# MotorCellOne.net
KiCad netlist of a schematic drawn in Altium Designer
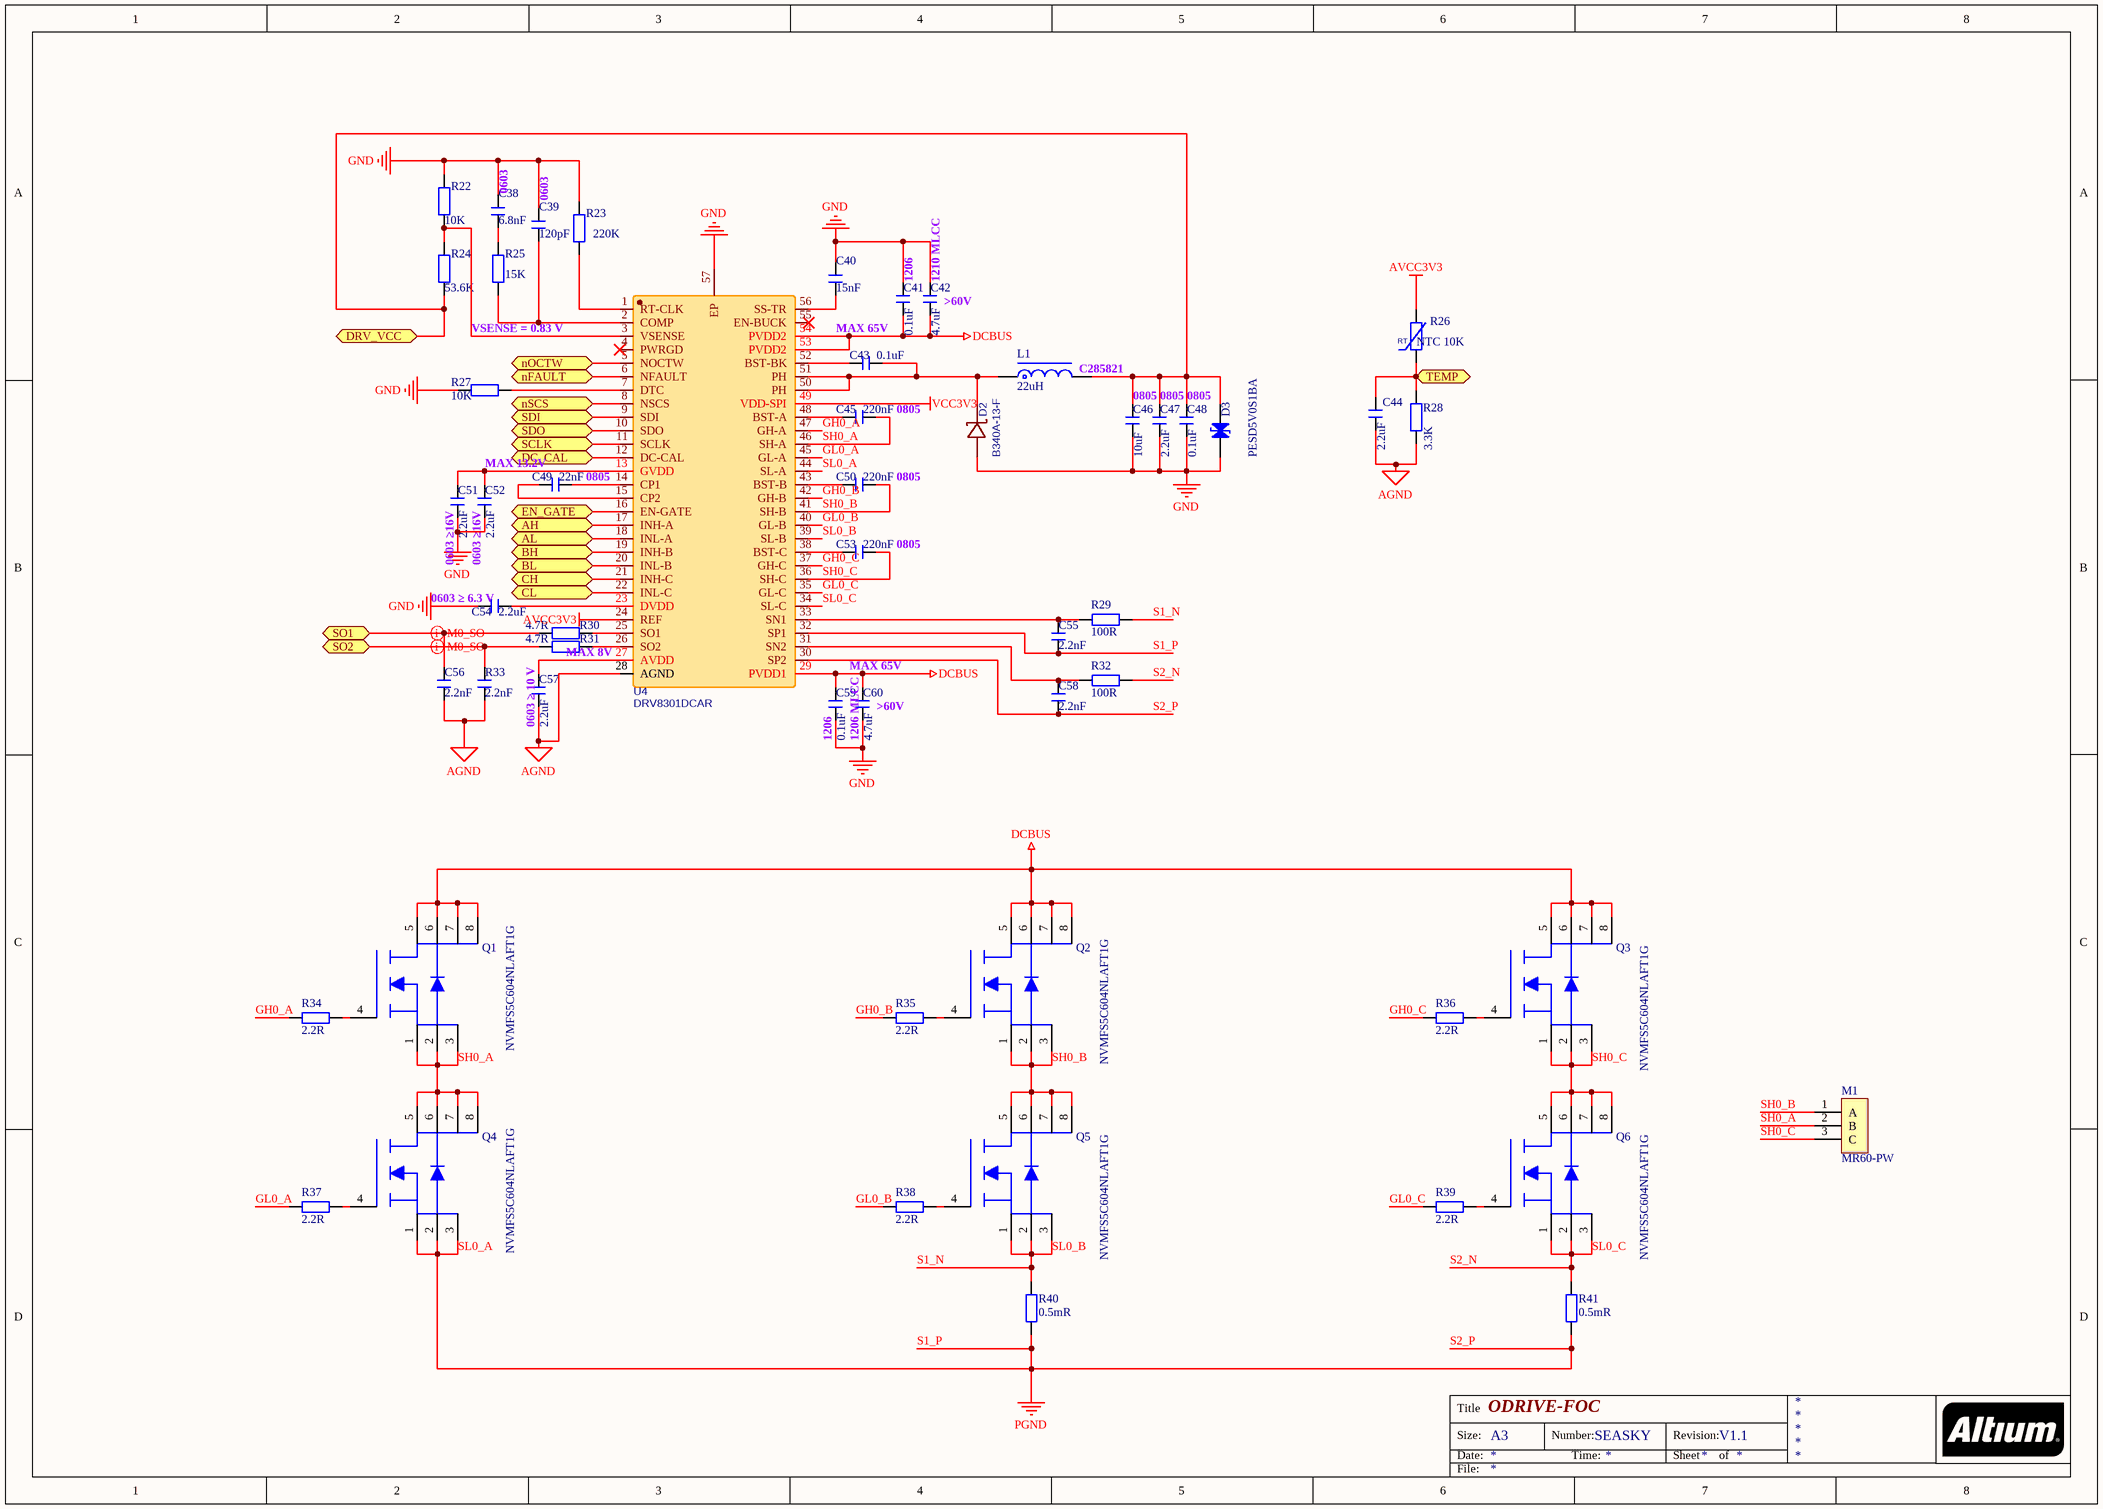
[diagram p0: MotorCellOne.SchDoc]

(export (version "E")
  (design (tool "Eeschema 10.0.6"))
  (components
    (comp (ref "C38")
      (value "6.8nF")
      (footprint "C 0603_L")
      (description "贴片电容")
      (libsource (lib "0.1 - 电阻-电容-电感") (part "C"))
    )
    (comp (ref "C39")
      (value "120pF")
      (footprint "C 0603_L")
      (description "贴片电容")
      (libsource (lib "0.1 - 电阻-电容-电感") (part "C"))
    )
    (comp (ref "C40")
      (value "15nF")
      (footprint "C 0603_L")
      (description "贴片电容")
      (libsource (lib "0.1 - 电阻-电容-电感") (part "C"))
    )
    (comp (ref "C41")
      (value "0.1uF")
      (footprint "C 1206_L")
      (description "贴片电容")
      (libsource (lib "0.1 - 电阻-电容-电感") (part "C"))
    )
    (comp (ref "C42")
      (value "4.7uF")
      (footprint "C 1210_L")
      (description "贴片电容")
      (libsource (lib "0.1 - 电阻-电容-电感") (part "C"))
    )
    (comp (ref "C43")
      (value "0.1uF")
      (footprint "C 0603_L")
      (description "贴片电容")
      (libsource (lib "0.1 - 电阻-电容-电感") (part "C"))
    )
    (comp (ref "C44")
      (value "2.2uF")
      (footprint "C 0603_L")
      (description "贴片电容")
      (libsource (lib "0.1 - 电阻-电容-电感") (part "C"))
    )
    (comp (ref "C45")
      (value "220nF")
      (footprint "C 0805_L")
      (description "贴片电容")
      (libsource (lib "0.1 - 电阻-电容-电感") (part "C"))
    )
    (comp (ref "C46")
      (value "10uF")
      (footprint "C 0805_L")
      (description "贴片电容")
      (libsource (lib "0.1 - 电阻-电容-电感") (part "C"))
    )
    (comp (ref "C47")
      (value "2.2uF")
      (footprint "C 0805_L")
      (description "贴片电容")
      (libsource (lib "0.1 - 电阻-电容-电感") (part "C"))
    )
    (comp (ref "C48")
      (value "0.1uF")
      (footprint "C 0805_L")
      (description "贴片电容")
      (libsource (lib "0.1 - 电阻-电容-电感") (part "C"))
    )
    (comp (ref "C49")
      (value "22nF")
      (footprint "C 0805_L")
      (description "贴片电容")
      (libsource (lib "0.1 - 电阻-电容-电感") (part "C"))
    )
    (comp (ref "C50")
      (value "220nF")
      (footprint "C 0805_L")
      (description "贴片电容")
      (libsource (lib "0.1 - 电阻-电容-电感") (part "C"))
    )
    (comp (ref "C51")
      (value "2.2uF")
      (footprint "C 0603_L")
      (description "贴片电容")
      (libsource (lib "0.1 - 电阻-电容-电感") (part "C"))
    )
    (comp (ref "C52")
      (value "2.2uF")
      (footprint "C 0603_L")
      (description "贴片电容")
      (libsource (lib "0.1 - 电阻-电容-电感") (part "C"))
    )
    (comp (ref "C53")
      (value "220nF")
      (footprint "C 0805_L")
      (description "贴片电容")
      (libsource (lib "0.1 - 电阻-电容-电感") (part "C"))
    )
    (comp (ref "C54")
      (value "2.2uF")
      (footprint "C 0603_L")
      (description "贴片电容")
      (libsource (lib "0.1 - 电阻-电容-电感") (part "C"))
    )
    (comp (ref "C55")
      (value "2.2nF")
      (footprint "C 0603_L")
      (description "贴片电容")
      (libsource (lib "0.1 - 电阻-电容-电感") (part "C"))
    )
    (comp (ref "C56")
      (value "2.2nF")
      (footprint "C 0603_L")
      (description "贴片电容")
      (libsource (lib "0.1 - 电阻-电容-电感") (part "C"))
    )
    (comp (ref "C57")
      (value "2.2uF")
      (footprint "C 0603_L")
      (description "贴片电容")
      (libsource (lib "0.1 - 电阻-电容-电感") (part "C"))
    )
    (comp (ref "C58")
      (value "2.2nF")
      (footprint "C 0603_L")
      (description "贴片电容")
      (libsource (lib "0.1 - 电阻-电容-电感") (part "C"))
    )
    (comp (ref "C59")
      (value "0.1uF")
      (footprint "C 1206_L")
      (description "贴片电容")
      (libsource (lib "0.1 - 电阻-电容-电感") (part "C"))
    )
    (comp (ref "C60")
      (value "4.7uF")
      (footprint "C 1210_L")
      (description "贴片电容")
      (libsource (lib "0.1 - 电阻-电容-电感") (part "C"))
    )
    (comp (ref "D2")
      (value "B340A-13-F")
      (footprint "SMA_L4.4-W2.6-LS5.0-RD")
      (fields (field (name "BOM_SUPPLIER PART") "C85098"))
      (libsource (lib "mx_pcb_library") (part "B340A-13-F"))
    )
    (comp (ref "D3")
      (value "PESD5V0S1BA")
      (footprint "SOD-323")
      (description "PESD5V0S1BA、ESD二极管、5V")
      (libsource (lib "0.2 -  二极管-整流桥") (part "PESD5V0S1BA"))
    )
    (comp (ref "L1")
      (value "22uH")
      (footprint "CD53")
      (description "CD系列贴片线绕功率电感")
      (libsource (lib "0.1 - 电阻-电容-电感") (part "L-SMD"))
    )
    (comp (ref "M1")
      (value "MR60-PW")
      (footprint "MR30-PW")
      (libsource (lib "mx_pcb_library") (part "MR60-PW"))
    )
    (comp (ref "Q1")
      (value "NVMFS5C604NLAFT1G")
      (footprint "PG-TDSON-8_L5.0-W6.0-P1.27-LS6.2-BL-EP")
      (libsource (lib "mx_pcb_library") (part "BSC037N08NS5ATMA1"))
    )
    (comp (ref "Q2")
      (value "NVMFS5C604NLAFT1G")
      (footprint "PG-TDSON-8_L5.0-W6.0-P1.27-LS6.2-BL-EP")
      (libsource (lib "mx_pcb_library") (part "BSC037N08NS5ATMA1"))
    )
    (comp (ref "Q3")
      (value "NVMFS5C604NLAFT1G")
      (footprint "PG-TDSON-8_L5.0-W6.0-P1.27-LS6.2-BL-EP")
      (libsource (lib "mx_pcb_library") (part "BSC037N08NS5ATMA1"))
    )
    (comp (ref "Q4")
      (value "NVMFS5C604NLAFT1G")
      (footprint "PG-TDSON-8_L5.0-W6.0-P1.27-LS6.2-BL-EP")
      (libsource (lib "mx_pcb_library") (part "BSC037N08NS5ATMA1"))
    )
    (comp (ref "Q5")
      (value "NVMFS5C604NLAFT1G")
      (footprint "PG-TDSON-8_L5.0-W6.0-P1.27-LS6.2-BL-EP")
      (libsource (lib "mx_pcb_library") (part "BSC037N08NS5ATMA1"))
    )
    (comp (ref "Q6")
      (value "NVMFS5C604NLAFT1G")
      (footprint "PG-TDSON-8_L5.0-W6.0-P1.27-LS6.2-BL-EP")
      (libsource (lib "mx_pcb_library") (part "BSC037N08NS5ATMA1"))
    )
    (comp (ref "R22")
      (value "10K")
      (footprint "R 0603_L")
      (description "贴片电阻")
      (libsource (lib "0.1 - 电阻-电容-电感") (part "R"))
    )
    (comp (ref "R23")
      (value "220K")
      (footprint "R 0603_L")
      (description "贴片电阻")
      (libsource (lib "0.1 - 电阻-电容-电感") (part "R"))
    )
    (comp (ref "R24")
      (value "53.6K")
      (footprint "R 0603_L")
      (description "贴片电阻")
      (libsource (lib "0.1 - 电阻-电容-电感") (part "R"))
    )
    (comp (ref "R25")
      (value "15K")
      (footprint "R 0603_L")
      (description "贴片电阻")
      (libsource (lib "0.1 - 电阻-电容-电感") (part "R"))
    )
    (comp (ref "R26")
      (value "NTC 10K")
      (footprint "R 0805-HP_L")
      (description "热敏电阻")
      (libsource (lib "0.1 - 电阻-电容-电感") (part "RT"))
    )
    (comp (ref "R27")
      (value "10K")
      (footprint "R 0603_L")
      (description "贴片电阻")
      (libsource (lib "0.1 - 电阻-电容-电感") (part "R"))
    )
    (comp (ref "R28")
      (value "3.3K")
      (footprint "R 0805_L")
      (description "贴片电阻")
      (libsource (lib "0.1 - 电阻-电容-电感") (part "R"))
    )
    (comp (ref "R29")
      (value "100R")
      (footprint "R 0603_L")
      (description "贴片电阻")
      (libsource (lib "0.1 - 电阻-电容-电感") (part "R"))
    )
    (comp (ref "R30")
      (value "4.7R")
      (footprint "R 0603_L")
      (description "贴片电阻")
      (libsource (lib "0.1 - 电阻-电容-电感") (part "R"))
    )
    (comp (ref "R31")
      (value "4.7R")
      (footprint "R 0603_L")
      (description "贴片电阻")
      (libsource (lib "0.1 - 电阻-电容-电感") (part "R"))
    )
    (comp (ref "R32")
      (value "100R")
      (footprint "R 0603_L")
      (description "贴片电阻")
      (libsource (lib "0.1 - 电阻-电容-电感") (part "R"))
    )
    (comp (ref "R33")
      (value "2.2nF")
      (footprint "C 0603_L")
      (description "贴片电容")
      (libsource (lib "0.1 - 电阻-电容-电感") (part "C"))
    )
    (comp (ref "R34")
      (value "2.2R")
      (footprint "R 0603_L")
      (description "贴片电阻")
      (libsource (lib "0.1 - 电阻-电容-电感") (part "R"))
    )
    (comp (ref "R35")
      (value "2.2R")
      (footprint "R 0603_L")
      (description "贴片电阻")
      (libsource (lib "0.1 - 电阻-电容-电感") (part "R"))
    )
    (comp (ref "R36")
      (value "2.2R")
      (footprint "R 0603_L")
      (description "贴片电阻")
      (libsource (lib "0.1 - 电阻-电容-电感") (part "R"))
    )
    (comp (ref "R37")
      (value "2.2R")
      (footprint "R 0603_L")
      (description "贴片电阻")
      (libsource (lib "0.1 - 电阻-电容-电感") (part "R"))
    )
    (comp (ref "R38")
      (value "2.2R")
      (footprint "R 0603_L")
      (description "贴片电阻")
      (libsource (lib "0.1 - 电阻-电容-电感") (part "R"))
    )
    (comp (ref "R39")
      (value "2.2R")
      (footprint "R 0603_L")
      (description "贴片电阻")
      (libsource (lib "0.1 - 电阻-电容-电感") (part "R"))
    )
    (comp (ref "R40")
      (value "0.5mR")
      (footprint "R3920")
      (description "精密贴片电阻")
      (libsource (lib "0.1 - 电阻-电容-电感") (part "R-Precision"))
    )
    (comp (ref "R41")
      (value "0.5mR")
      (footprint "R3920")
      (description "精密贴片电阻")
      (libsource (lib "0.1 - 电阻-电容-电感") (part "R-Precision"))
    )
    (comp (ref "U4")
      (value "DRV8301DCAR")
      (footprint "HTSSOP-56_L14.0-W6.0-P0.50-LS8.0-BL")
      (fields (field (name "BOM_SUPPLIER PART") "C98969") (field (name "CONTRIBUTOR") "LCSC"))
      (libsource (lib "mx_pcb_library") (part "DRV8301DCAR"))
    )
  )
  (nets
    (net (code "1") (name "/AH") (class "Default")
      (node (ref "U4") (pin "17") (pinfunction "INH-A_17") (pintype "passive"))
    )
    (net (code "2") (name "/AL") (class "Default")
      (node (ref "U4") (pin "18") (pinfunction "INL-A_18") (pintype "passive"))
    )
    (net (code "3") (name "/BH") (class "Default")
      (node (ref "U4") (pin "19") (pinfunction "INH-B_19") (pintype "passive"))
    )
    (net (code "4") (name "/BL") (class "Default")
      (node (ref "U4") (pin "20") (pinfunction "INL-B_20") (pintype "passive"))
    )
    (net (code "5") (name "/CH") (class "Default")
      (node (ref "U4") (pin "21") (pinfunction "INH-C_21") (pintype "passive"))
    )
    (net (code "6") (name "/CL") (class "Default")
      (node (ref "U4") (pin "22") (pinfunction "INL-C_22") (pintype "passive"))
    )
    (net (code "7") (name "/DC_CAL") (class "Default")
      (node (ref "U4") (pin "12") (pinfunction "DC-CAL_12") (pintype "passive"))
    )
    (net (code "8") (name "/DRV_VCC") (class "Default")
      (node (ref "C46") (pin "2") (pinfunction "2_2") (pintype "passive"))
      (node (ref "C47") (pin "2") (pinfunction "2_2") (pintype "passive"))
      (node (ref "C48") (pin "2") (pinfunction "2_2") (pintype "passive"))
      (node (ref "D3") (pin "1") (pinfunction "A_1") (pintype "passive"))
      (node (ref "L1") (pin "2") (pinfunction "2_2") (pintype "passive"))
      (node (ref "R24") (pin "1") (pinfunction "1_1") (pintype "passive"))
    )
    (net (code "9") (name "/EN_GATE") (class "Default")
      (node (ref "U4") (pin "16") (pinfunction "EN-GATE_16") (pintype "passive"))
    )
    (net (code "10") (name "/GH0_A") (class "Default")
      (node (ref "R34") (pin "1") (pinfunction "1_1") (pintype "passive"))
      (node (ref "U4") (pin "47") (pinfunction "GH-A_47") (pintype "passive"))
    )
    (net (code "11") (name "/GH0_B") (class "Default")
      (node (ref "R35") (pin "1") (pinfunction "1_1") (pintype "passive"))
      (node (ref "U4") (pin "42") (pinfunction "GH-B_42") (pintype "passive"))
    )
    (net (code "12") (name "/GH0_C") (class "Default")
      (node (ref "R36") (pin "1") (pinfunction "1_1") (pintype "passive"))
      (node (ref "U4") (pin "37") (pinfunction "GH-C_37") (pintype "passive"))
    )
    (net (code "13") (name "/GL0_A") (class "Default")
      (node (ref "R37") (pin "1") (pinfunction "1_1") (pintype "passive"))
      (node (ref "U4") (pin "45") (pinfunction "GL-A_45") (pintype "passive"))
    )
    (net (code "14") (name "/GL0_B") (class "Default")
      (node (ref "R38") (pin "1") (pinfunction "1_1") (pintype "passive"))
      (node (ref "U4") (pin "40") (pinfunction "GL-B_40") (pintype "passive"))
    )
    (net (code "15") (name "/GL0_C") (class "Default")
      (node (ref "R39") (pin "1") (pinfunction "1_1") (pintype "passive"))
      (node (ref "U4") (pin "35") (pinfunction "GL-C_35") (pintype "passive"))
    )
    (net (code "16") (name "/S1_N") (class "Default")
      (node (ref "Q5") (pin "1") (pinfunction "1_1") (pintype "passive"))
      (node (ref "Q5") (pin "2") (pinfunction "2_2") (pintype "passive"))
      (node (ref "Q5") (pin "3") (pinfunction "3_3") (pintype "passive"))
      (node (ref "R29") (pin "2") (pinfunction "2_2") (pintype "passive"))
      (node (ref "R40") (pin "2") (pinfunction "2_2") (pintype "passive"))
      (node (ref "U4") (pin "39") (pinfunction "SL-B_39") (pintype "passive"))
    )
    (net (code "17") (name "/S2_N") (class "Default")
      (node (ref "Q6") (pin "1") (pinfunction "1_1") (pintype "passive"))
      (node (ref "Q6") (pin "2") (pinfunction "2_2") (pintype "passive"))
      (node (ref "Q6") (pin "3") (pinfunction "3_3") (pintype "passive"))
      (node (ref "R32") (pin "2") (pinfunction "2_2") (pintype "passive"))
      (node (ref "R41") (pin "2") (pinfunction "2_2") (pintype "passive"))
      (node (ref "U4") (pin "34") (pinfunction "SL-C_34") (pintype "passive"))
    )
    (net (code "18") (name "/SCLK") (class "Default")
      (node (ref "U4") (pin "11") (pinfunction "SCLK_11") (pintype "passive"))
    )
    (net (code "19") (name "/SDI") (class "Default")
      (node (ref "U4") (pin "9") (pinfunction "SDI_9") (pintype "passive"))
    )
    (net (code "20") (name "/SDO") (class "Default")
      (node (ref "U4") (pin "10") (pinfunction "SDO_10") (pintype "passive"))
    )
    (net (code "21") (name "/SH0_A") (class "Default")
      (node (ref "C45") (pin "2") (pinfunction "2_2") (pintype "passive"))
      (node (ref "M1") (pin "2") (pinfunction "B_2") (pintype "passive"))
      (node (ref "Q1") (pin "1") (pinfunction "1_1") (pintype "passive"))
      (node (ref "Q1") (pin "2") (pinfunction "2_2") (pintype "passive"))
      (node (ref "Q1") (pin "3") (pinfunction "3_3") (pintype "passive"))
      (node (ref "Q4") (pin "5") (pinfunction "5_5") (pintype "passive"))
      (node (ref "Q4") (pin "6") (pinfunction "6_6") (pintype "passive"))
      (node (ref "Q4") (pin "7") (pinfunction "7_7") (pintype "passive"))
      (node (ref "Q4") (pin "8") (pinfunction "8_8") (pintype "passive"))
      (node (ref "U4") (pin "46") (pinfunction "SH-A_46") (pintype "passive"))
    )
    (net (code "22") (name "/SH0_B") (class "Default")
      (node (ref "C50") (pin "2") (pinfunction "2_2") (pintype "passive"))
      (node (ref "M1") (pin "1") (pinfunction "A_1") (pintype "passive"))
      (node (ref "Q2") (pin "1") (pinfunction "1_1") (pintype "passive"))
      (node (ref "Q2") (pin "2") (pinfunction "2_2") (pintype "passive"))
      (node (ref "Q2") (pin "3") (pinfunction "3_3") (pintype "passive"))
      (node (ref "Q5") (pin "5") (pinfunction "5_5") (pintype "passive"))
      (node (ref "Q5") (pin "6") (pinfunction "6_6") (pintype "passive"))
      (node (ref "Q5") (pin "7") (pinfunction "7_7") (pintype "passive"))
      (node (ref "Q5") (pin "8") (pinfunction "8_8") (pintype "passive"))
      (node (ref "U4") (pin "41") (pinfunction "SH-B_41") (pintype "passive"))
    )
    (net (code "23") (name "/SH0_C") (class "Default")
      (node (ref "C53") (pin "2") (pinfunction "2_2") (pintype "passive"))
      (node (ref "M1") (pin "3") (pinfunction "C_3") (pintype "passive"))
      (node (ref "Q3") (pin "1") (pinfunction "1_1") (pintype "passive"))
      (node (ref "Q3") (pin "2") (pinfunction "2_2") (pintype "passive"))
      (node (ref "Q3") (pin "3") (pinfunction "3_3") (pintype "passive"))
      (node (ref "Q6") (pin "5") (pinfunction "5_5") (pintype "passive"))
      (node (ref "Q6") (pin "6") (pinfunction "6_6") (pintype "passive"))
      (node (ref "Q6") (pin "7") (pinfunction "7_7") (pintype "passive"))
      (node (ref "Q6") (pin "8") (pinfunction "8_8") (pintype "passive"))
      (node (ref "U4") (pin "36") (pinfunction "SH-C_36") (pintype "passive"))
    )
    (net (code "24") (name "/SO1") (class "Default")
      (node (ref "C56") (pin "2") (pinfunction "2_2") (pintype "passive"))
      (node (ref "R30") (pin "1") (pinfunction "1_1") (pintype "passive"))
    )
    (net (code "25") (name "/SO2") (class "Default")
      (node (ref "R31") (pin "1") (pinfunction "1_1") (pintype "passive"))
      (node (ref "R33") (pin "2") (pinfunction "2_2") (pintype "passive"))
    )
    (net (code "26") (name "/TEMP") (class "Default")
      (node (ref "C44") (pin "1") (pinfunction "1_1") (pintype "passive"))
      (node (ref "R26") (pin "1") (pinfunction "1_1") (pintype "passive"))
      (node (ref "R28") (pin "2") (pinfunction "2_2") (pintype "passive"))
    )
    (net (code "27") (name "/nFAULT") (class "Default")
      (node (ref "U4") (pin "6") (pinfunction "NFAULT_6") (pintype "passive"))
    )
    (net (code "28") (name "/nOCTW") (class "Default")
      (node (ref "U4") (pin "5") (pinfunction "NOCTW_5") (pintype "passive"))
    )
    (net (code "29") (name "/nSCS") (class "Default")
      (node (ref "U4") (pin "8") (pinfunction "NSCS_8") (pintype "passive"))
    )
    (net (code "30") (name "AGND") (class "Default")
      (node (ref "C44") (pin "2") (pinfunction "2_2") (pintype "passive"))
      (node (ref "C56") (pin "1") (pinfunction "1_1") (pintype "passive"))
      (node (ref "C57") (pin "1") (pinfunction "1_1") (pintype "passive"))
      (node (ref "R28") (pin "1") (pinfunction "1_1") (pintype "passive"))
      (node (ref "R33") (pin "1") (pinfunction "1_1") (pintype "passive"))
      (node (ref "U4") (pin "28") (pinfunction "AGND_28") (pintype "passive"))
    )
    (net (code "31") (name "AVCC3V3") (class "Default")
      (node (ref "R26") (pin "2") (pinfunction "2_2") (pintype "passive"))
      (node (ref "U4") (pin "24") (pinfunction "REF_24") (pintype "passive"))
    )
    (net (code "32") (name "DCBUS") (class "Default")
      (node (ref "C41") (pin "1") (pinfunction "1_1") (pintype "passive"))
      (node (ref "C42") (pin "1") (pinfunction "1_1") (pintype "passive"))
      (node (ref "C59") (pin "2") (pinfunction "2_2") (pintype "passive"))
      (node (ref "C60") (pin "2") (pinfunction "2_2") (pintype "passive"))
      (node (ref "Q1") (pin "5") (pinfunction "5_5") (pintype "passive"))
      (node (ref "Q1") (pin "6") (pinfunction "6_6") (pintype "passive"))
      (node (ref "Q1") (pin "7") (pinfunction "7_7") (pintype "passive"))
      (node (ref "Q1") (pin "8") (pinfunction "8_8") (pintype "passive"))
      (node (ref "Q2") (pin "5") (pinfunction "5_5") (pintype "passive"))
      (node (ref "Q2") (pin "6") (pinfunction "6_6") (pintype "passive"))
      (node (ref "Q2") (pin "7") (pinfunction "7_7") (pintype "passive"))
      (node (ref "Q2") (pin "8") (pinfunction "8_8") (pintype "passive"))
      (node (ref "Q3") (pin "5") (pinfunction "5_5") (pintype "passive"))
      (node (ref "Q3") (pin "6") (pinfunction "6_6") (pintype "passive"))
      (node (ref "Q3") (pin "7") (pinfunction "7_7") (pintype "passive"))
      (node (ref "Q3") (pin "8") (pinfunction "8_8") (pintype "passive"))
      (node (ref "U4") (pin "29") (pinfunction "PVDD1_29") (pintype "passive"))
      (node (ref "U4") (pin "53") (pinfunction "PVDD2_53") (pintype "passive"))
      (node (ref "U4") (pin "54") (pinfunction "PVDD2_54") (pintype "passive"))
    )
    (net (code "33") (name "GND") (class "Default")
      (node (ref "C38") (pin "1") (pinfunction "1_1") (pintype "passive"))
      (node (ref "C39") (pin "1") (pinfunction "1_1") (pintype "passive"))
      (node (ref "C40") (pin "1") (pinfunction "1_1") (pintype "passive"))
      (node (ref "C41") (pin "2") (pinfunction "2_2") (pintype "passive"))
      (node (ref "C42") (pin "2") (pinfunction "2_2") (pintype "passive"))
      (node (ref "C46") (pin "1") (pinfunction "1_1") (pintype "passive"))
      (node (ref "C47") (pin "1") (pinfunction "1_1") (pintype "passive"))
      (node (ref "C48") (pin "1") (pinfunction "1_1") (pintype "passive"))
      (node (ref "C51") (pin "1") (pinfunction "1_1") (pintype "passive"))
      (node (ref "C52") (pin "1") (pinfunction "1_1") (pintype "passive"))
      (node (ref "C54") (pin "1") (pinfunction "1_1") (pintype "passive"))
      (node (ref "C59") (pin "1") (pinfunction "1_1") (pintype "passive"))
      (node (ref "C60") (pin "1") (pinfunction "1_1") (pintype "passive"))
      (node (ref "D2") (pin "2") (pinfunction "A_2") (pintype "passive"))
      (node (ref "D3") (pin "2") (pinfunction "K_2") (pintype "passive"))
      (node (ref "R22") (pin "2") (pinfunction "2_2") (pintype "passive"))
      (node (ref "R23") (pin "2") (pinfunction "2_2") (pintype "passive"))
      (node (ref "R27") (pin "2") (pinfunction "2_2") (pintype "passive"))
      (node (ref "U4") (pin "57") (pinfunction "EP_57") (pintype "passive"))
    )
    (net (code "34") (name "Net-(C38-Pad2)") (class "Default")
      (node (ref "C38") (pin "2") (pinfunction "2_2") (pintype "passive"))
      (node (ref "R25") (pin "2") (pinfunction "2_2") (pintype "passive"))
    )
    (net (code "35") (name "Net-(D2-K)") (class "Default")
      (node (ref "C43") (pin "1") (pinfunction "1_1") (pintype "passive"))
      (node (ref "D2") (pin "1") (pinfunction "K_1") (pintype "passive"))
      (node (ref "L1") (pin "1") (pinfunction "1_1") (pintype "passive"))
      (node (ref "U4") (pin "50") (pinfunction "PH_50") (pintype "passive"))
      (node (ref "U4") (pin "51") (pinfunction "PH_51") (pintype "passive"))
    )
    (net (code "36") (name "Net-(Q1-Pad4)") (class "Default")
      (node (ref "Q1") (pin "4") (pinfunction "4_4") (pintype "passive"))
      (node (ref "R34") (pin "2") (pinfunction "2_2") (pintype "passive"))
    )
    (net (code "37") (name "Net-(Q2-Pad4)") (class "Default")
      (node (ref "Q2") (pin "4") (pinfunction "4_4") (pintype "passive"))
      (node (ref "R35") (pin "2") (pinfunction "2_2") (pintype "passive"))
    )
    (net (code "38") (name "Net-(Q3-Pad4)") (class "Default")
      (node (ref "Q3") (pin "4") (pinfunction "4_4") (pintype "passive"))
      (node (ref "R36") (pin "2") (pinfunction "2_2") (pintype "passive"))
    )
    (net (code "39") (name "Net-(Q4-Pad4)") (class "Default")
      (node (ref "Q4") (pin "4") (pinfunction "4_4") (pintype "passive"))
      (node (ref "R37") (pin "2") (pinfunction "2_2") (pintype "passive"))
    )
    (net (code "40") (name "Net-(Q5-Pad4)") (class "Default")
      (node (ref "Q5") (pin "4") (pinfunction "4_4") (pintype "passive"))
      (node (ref "R38") (pin "2") (pinfunction "2_2") (pintype "passive"))
    )
    (net (code "41") (name "Net-(Q6-Pad4)") (class "Default")
      (node (ref "Q6") (pin "4") (pinfunction "4_4") (pintype "passive"))
      (node (ref "R39") (pin "2") (pinfunction "2_2") (pintype "passive"))
    )
    (net (code "42") (name "Net-(U4-AVDD)") (class "Default")
      (node (ref "C57") (pin "2") (pinfunction "2_2") (pintype "passive"))
      (node (ref "U4") (pin "27") (pinfunction "AVDD_27") (pintype "passive"))
    )
    (net (code "43") (name "Net-(U4-BST-A)") (class "Default")
      (node (ref "C45") (pin "1") (pinfunction "1_1") (pintype "passive"))
      (node (ref "U4") (pin "48") (pinfunction "BST-A_48") (pintype "passive"))
    )
    (net (code "44") (name "Net-(U4-BST-B)") (class "Default")
      (node (ref "C50") (pin "1") (pinfunction "1_1") (pintype "passive"))
      (node (ref "U4") (pin "43") (pinfunction "BST-B_43") (pintype "passive"))
    )
    (net (code "45") (name "Net-(U4-BST-BK)") (class "Default")
      (node (ref "C43") (pin "2") (pinfunction "2_2") (pintype "passive"))
      (node (ref "U4") (pin "52") (pinfunction "BST-BK_52") (pintype "passive"))
    )
    (net (code "46") (name "Net-(U4-BST-C)") (class "Default")
      (node (ref "C53") (pin "1") (pinfunction "1_1") (pintype "passive"))
      (node (ref "U4") (pin "38") (pinfunction "BST-C_38") (pintype "passive"))
    )
    (net (code "47") (name "Net-(U4-COMP)") (class "Default")
      (node (ref "C39") (pin "2") (pinfunction "2_2") (pintype "passive"))
      (node (ref "R25") (pin "1") (pinfunction "1_1") (pintype "passive"))
      (node (ref "U4") (pin "2") (pinfunction "COMP_2") (pintype "passive"))
    )
    (net (code "48") (name "Net-(U4-CP1)") (class "Default")
      (node (ref "C49") (pin "1") (pinfunction "1_1") (pintype "passive"))
      (node (ref "U4") (pin "14") (pinfunction "CP1_14") (pintype "passive"))
    )
    (net (code "49") (name "Net-(U4-CP2)") (class "Default")
      (node (ref "C49") (pin "2") (pinfunction "2_2") (pintype "passive"))
      (node (ref "U4") (pin "15") (pinfunction "CP2_15") (pintype "passive"))
    )
    (net (code "50") (name "Net-(U4-DTC)") (class "Default")
      (node (ref "R27") (pin "1") (pinfunction "1_1") (pintype "passive"))
      (node (ref "U4") (pin "7") (pinfunction "DTC_7") (pintype "passive"))
    )
    (net (code "51") (name "Net-(U4-DVDD)") (class "Default")
      (node (ref "C54") (pin "2") (pinfunction "2_2") (pintype "passive"))
      (node (ref "U4") (pin "23") (pinfunction "DVDD_23") (pintype "passive"))
    )
    (net (code "52") (name "Net-(U4-GVDD)") (class "Default")
      (node (ref "C51") (pin "2") (pinfunction "2_2") (pintype "passive"))
      (node (ref "C52") (pin "2") (pinfunction "2_2") (pintype "passive"))
      (node (ref "U4") (pin "13") (pinfunction "GVDD_13") (pintype "passive"))
    )
    (net (code "53") (name "Net-(U4-RT-CLK)") (class "Default")
      (node (ref "R23") (pin "1") (pinfunction "1_1") (pintype "passive"))
      (node (ref "U4") (pin "1") (pinfunction "RT-CLK_1") (pintype "passive"))
    )
    (net (code "54") (name "Net-(U4-SN1)") (class "Default")
      (node (ref "C55") (pin "2") (pinfunction "2_2") (pintype "passive"))
      (node (ref "R29") (pin "1") (pinfunction "1_1") (pintype "passive"))
      (node (ref "U4") (pin "33") (pinfunction "SN1_33") (pintype "passive"))
    )
    (net (code "55") (name "Net-(U4-SN2)") (class "Default")
      (node (ref "C58") (pin "2") (pinfunction "2_2") (pintype "passive"))
      (node (ref "R32") (pin "1") (pinfunction "1_1") (pintype "passive"))
      (node (ref "U4") (pin "31") (pinfunction "SN2_31") (pintype "passive"))
    )
    (net (code "56") (name "Net-(U4-SO1)") (class "Default")
      (node (ref "R30") (pin "2") (pinfunction "2_2") (pintype "passive"))
      (node (ref "U4") (pin "25") (pinfunction "SO1_25") (pintype "passive"))
    )
    (net (code "57") (name "Net-(U4-SO2)") (class "Default")
      (node (ref "R31") (pin "2") (pinfunction "2_2") (pintype "passive"))
      (node (ref "U4") (pin "26") (pinfunction "SO2_26") (pintype "passive"))
    )
    (net (code "58") (name "Net-(U4-SS-TR)") (class "Default")
      (node (ref "C40") (pin "2") (pinfunction "2_2") (pintype "passive"))
      (node (ref "U4") (pin "56") (pinfunction "SS-TR_56") (pintype "passive"))
    )
    (net (code "59") (name "Net-(U4-VSENSE)") (class "Default")
      (node (ref "R22") (pin "1") (pinfunction "1_1") (pintype "passive"))
      (node (ref "R24") (pin "2") (pinfunction "2_2") (pintype "passive"))
      (node (ref "U4") (pin "3") (pinfunction "VSENSE_3") (pintype "passive"))
    )
    (net (code "60") (name "PGND") (class "Default")
      (node (ref "C55") (pin "1") (pinfunction "1_1") (pintype "passive"))
      (node (ref "C58") (pin "1") (pinfunction "1_1") (pintype "passive"))
      (node (ref "Q4") (pin "1") (pinfunction "1_1") (pintype "passive"))
      (node (ref "Q4") (pin "2") (pinfunction "2_2") (pintype "passive"))
      (node (ref "Q4") (pin "3") (pinfunction "3_3") (pintype "passive"))
      (node (ref "R40") (pin "1") (pinfunction "1_1") (pintype "passive"))
      (node (ref "R41") (pin "1") (pinfunction "1_1") (pintype "passive"))
      (node (ref "U4") (pin "30") (pinfunction "SP2_30") (pintype "passive"))
      (node (ref "U4") (pin "32") (pinfunction "SP1_32") (pintype "passive"))
      (node (ref "U4") (pin "44") (pinfunction "SL-A_44") (pintype "passive"))
    )
    (net (code "61") (name "VCC3V3") (class "Default")
      (node (ref "U4") (pin "49") (pinfunction "VDD-SPI_49") (pintype "passive"))
    )
    (net (code "62") (name "unconnected-(U4-EN-BUCK-Pad55)") (class "Default")
      (node (ref "U4") (pin "55") (pinfunction "EN-BUCK_55") (pintype "passive+no_connect"))
    )
    (net (code "63") (name "unconnected-(U4-PWRGD-Pad4)") (class "Default")
      (node (ref "U4") (pin "4") (pinfunction "PWRGD_4") (pintype "passive+no_connect"))
    )
  )
)
